# LoRa_ST_v2_0.net
KiCad netlist of a schematic drawn in EAGLE
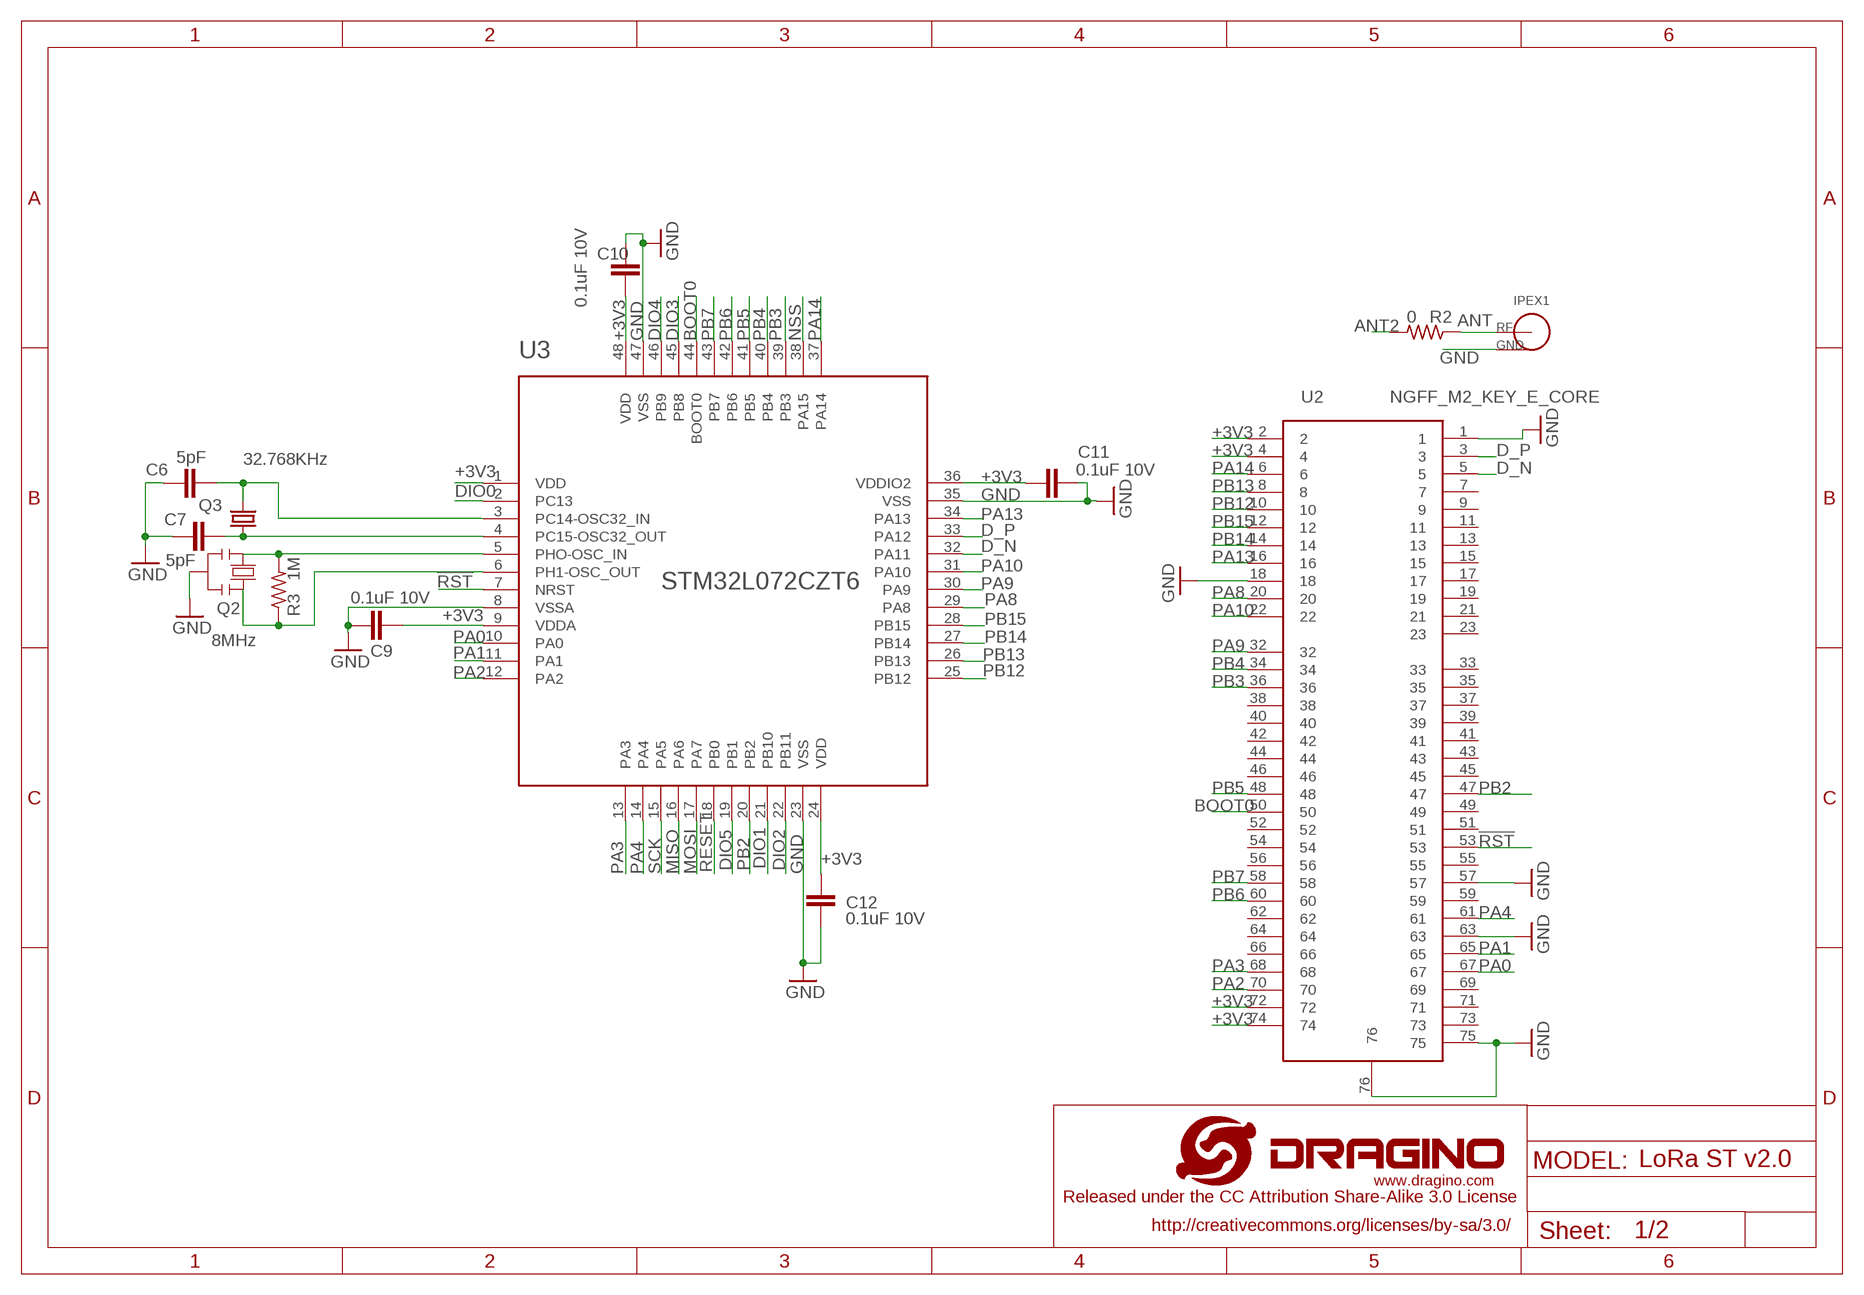
[diagram p0: schematic, sheet 1]
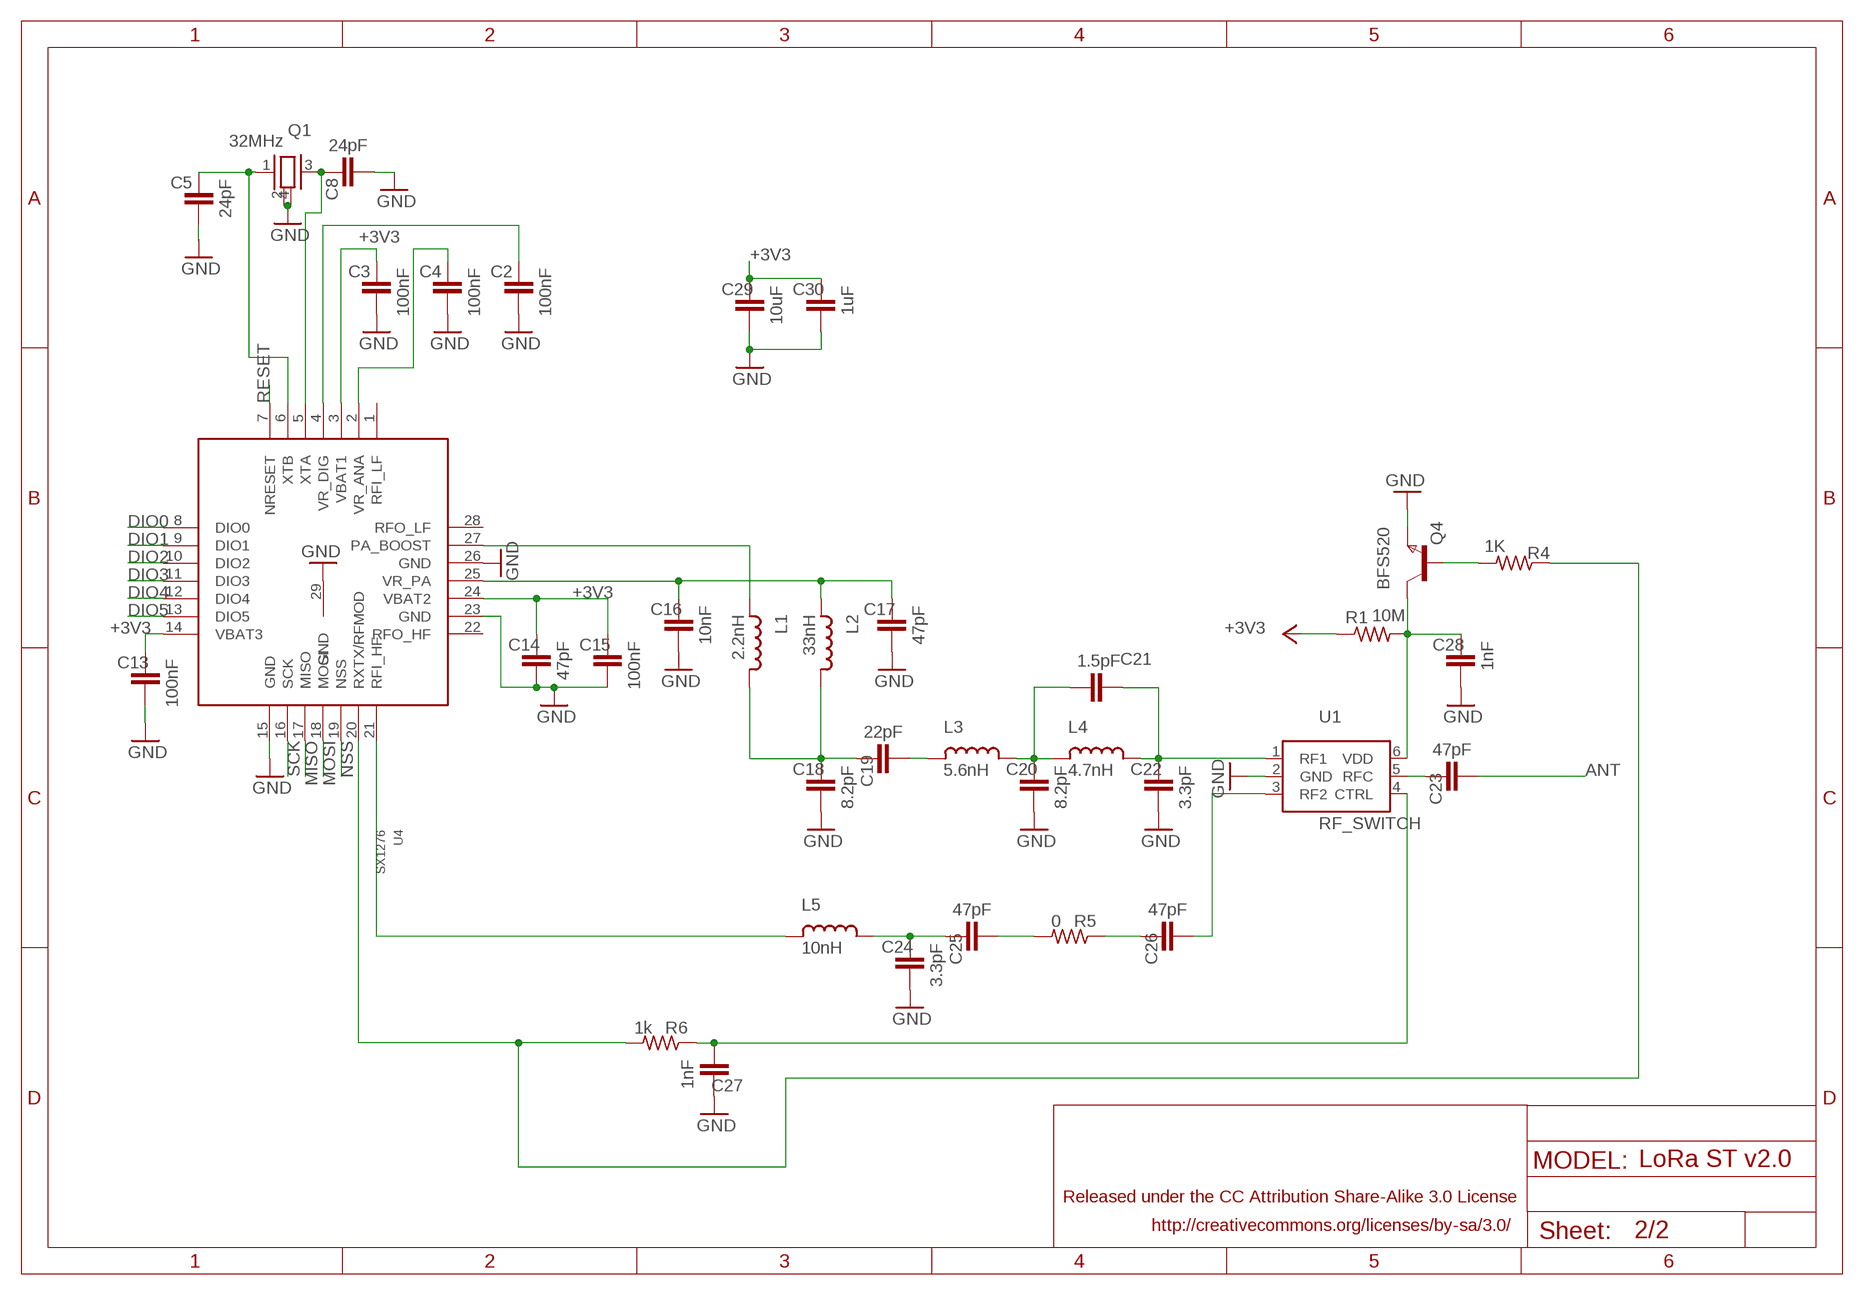
[diagram p1: schematic, sheet 2]

(export (version "E")
  (design (tool "Eeschema 10.0.6"))
  (components
    (comp (ref "C2")
      (value "100nF")
      (footprint "eagle-import:C0402")
      (libsource (lib "eagle-import") (part "C-EUC0402"))
    )
    (comp (ref "C3")
      (value "100nF")
      (footprint "eagle-import:C0402")
      (libsource (lib "eagle-import") (part "C-EUC0402"))
    )
    (comp (ref "C4")
      (value "100nF")
      (footprint "eagle-import:C0402")
      (libsource (lib "eagle-import") (part "C-EUC0402"))
    )
    (comp (ref "C5")
      (value "24pF")
      (footprint "eagle-import:C0402")
      (libsource (lib "eagle-import") (part "C-EUC0402"))
    )
    (comp (ref "C8")
      (value "24pF")
      (footprint "eagle-import:C0402")
      (libsource (lib "eagle-import") (part "C-EUC0402"))
    )
    (comp (ref "C13")
      (value "100nF")
      (footprint "eagle-import:C0402")
      (libsource (lib "eagle-import") (part "C-EUC0402"))
    )
    (comp (ref "C14")
      (value "47pF")
      (footprint "eagle-import:C0402")
      (libsource (lib "eagle-import") (part "C-EUC0402"))
    )
    (comp (ref "C15")
      (value "100nF")
      (footprint "eagle-import:C0402")
      (libsource (lib "eagle-import") (part "C-EUC0402"))
    )
    (comp (ref "C16")
      (value "10nF")
      (footprint "eagle-import:C0402")
      (libsource (lib "eagle-import") (part "C-EUC0402"))
    )
    (comp (ref "C17")
      (value "47pF")
      (footprint "eagle-import:C0402")
      (libsource (lib "eagle-import") (part "C-EUC0402"))
    )
    (comp (ref "C18")
      (value "8.2pF")
      (footprint "eagle-import:C0402")
      (libsource (lib "eagle-import") (part "C-EUC0402"))
    )
    (comp (ref "C19")
      (value "22pF")
      (footprint "eagle-import:C0402")
      (libsource (lib "eagle-import") (part "C-EUC0402"))
    )
    (comp (ref "C20")
      (value "8.2pF")
      (footprint "eagle-import:C0402")
      (libsource (lib "eagle-import") (part "C-EUC0402"))
    )
    (comp (ref "C21")
      (value "1.5pF")
      (footprint "eagle-import:C0402")
      (libsource (lib "eagle-import") (part "C-EUC0402"))
    )
    (comp (ref "C22")
      (value "3.3pF")
      (footprint "eagle-import:C0402")
      (libsource (lib "eagle-import") (part "C-EUC0402"))
    )
    (comp (ref "C23")
      (value "47pF")
      (footprint "eagle-import:C0402")
      (libsource (lib "eagle-import") (part "C-EUC0402"))
    )
    (comp (ref "C24")
      (value "3.3pF")
      (footprint "eagle-import:C0402")
      (libsource (lib "eagle-import") (part "C-EUC0402"))
    )
    (comp (ref "C25")
      (value "47pF")
      (footprint "eagle-import:C0402")
      (libsource (lib "eagle-import") (part "C-EUC0402"))
    )
    (comp (ref "C26")
      (value "47pF")
      (footprint "eagle-import:C0402")
      (libsource (lib "eagle-import") (part "C-EUC0402"))
    )
    (comp (ref "C27")
      (value "1nF")
      (footprint "eagle-import:C0402")
      (libsource (lib "eagle-import") (part "C-EUC0402"))
    )
    (comp (ref "C28")
      (value "1nF")
      (footprint "eagle-import:C0402")
      (libsource (lib "eagle-import") (part "C-EUC0402"))
    )
    (comp (ref "C29")
      (value "10uF")
      (footprint "eagle-import:C0805")
      (libsource (lib "eagle-import") (part "C-EUC0805"))
    )
    (comp (ref "C30")
      (value "1uF")
      (footprint "eagle-import:C0805")
      (libsource (lib "eagle-import") (part "C-EUC0805"))
    )
    (comp (ref "L1")
      (value "2.2nH")
      (footprint "eagle-import:I-0402")
      (libsource (lib "eagle-import") (part "I-EU0402"))
    )
    (comp (ref "L2")
      (value "33nH")
      (footprint "eagle-import:I-0402")
      (libsource (lib "eagle-import") (part "I-EU0402"))
    )
    (comp (ref "L3")
      (value "5.6nH")
      (footprint "eagle-import:I-0402")
      (libsource (lib "eagle-import") (part "I-EU0402"))
    )
    (comp (ref "L4")
      (value "4.7nH")
      (footprint "eagle-import:I-0402")
      (libsource (lib "eagle-import") (part "I-EU0402"))
    )
    (comp (ref "L5")
      (value "10nH")
      (footprint "eagle-import:I-0402")
      (libsource (lib "eagle-import") (part "I-EU0402"))
    )
    (comp (ref "Q1")
      (value "32MHz")
      (footprint "eagle-import:SMD-3225_4P")
      (libsource (lib "eagle-import") (part "Q"))
    )
    (comp (ref "Q4")
      (value "BFS520")
      (footprint "eagle-import:SOT323")
      (fields (field (name "MPN") "DSS4160U-7"))
      (libsource (lib "eagle-import") (part "NPNSOT323"))
    )
    (comp (ref "R1")
      (value "10M")
      (footprint "eagle-import:R0402")
      (libsource (lib "eagle-import") (part "R-US_R0402"))
    )
    (comp (ref "R4")
      (value "1K")
      (footprint "eagle-import:R0402")
      (libsource (lib "eagle-import") (part "R-US_R0402"))
    )
    (comp (ref "R5")
      (value "0")
      (footprint "eagle-import:R0402")
      (libsource (lib "eagle-import") (part "R-US_R0402"))
    )
    (comp (ref "R6")
      (value "1k")
      (footprint "eagle-import:R0402")
      (libsource (lib "eagle-import") (part "R-US_R0402"))
    )
    (comp (ref "U1")
      (value "RF_SWITCH")
      (footprint "eagle-import:SC70-6")
      (libsource (lib "eagle-import") (part "RF_SWITCH"))
    )
    (comp (ref "U4")
      (value "SX1276")
      (footprint "eagle-import:VQFN28_6X6MM")
      (libsource (lib "eagle-import") (part "SX1276"))
    )
    (comp (ref "C6")
      (value "5pF")
      (footprint "eagle-import:C0402")
      (libsource (lib "eagle-import") (part "C-EUC0402"))
    )
    (comp (ref "C7")
      (value "5pF")
      (footprint "eagle-import:C0402")
      (libsource (lib "eagle-import") (part "C-EUC0402"))
    )
    (comp (ref "C9")
      (value "0.1uF 10V")
      (footprint "eagle-import:C0402")
      (libsource (lib "eagle-import") (part "C-EUC0402"))
    )
    (comp (ref "C10")
      (value "0.1uF 10V")
      (footprint "eagle-import:C0402")
      (libsource (lib "eagle-import") (part "C-EUC0402"))
    )
    (comp (ref "C11")
      (value "0.1uF 10V")
      (footprint "eagle-import:C0402")
      (libsource (lib "eagle-import") (part "C-EUC0402"))
    )
    (comp (ref "C12")
      (value "0.1uF 10V")
      (footprint "eagle-import:C0402")
      (libsource (lib "eagle-import") (part "C-EUC0402"))
    )
    (comp (ref "IPEX1")
      (value "I-PEX4")
      (footprint "eagle-import:I-PEX4")
      (libsource (lib "eagle-import") (part "I-PEX4"))
    )
    (comp (ref "Q2")
      (value "8MHz")
      (footprint "eagle-import:RESONATOR")
      (libsource (lib "eagle-import") (part "RESONATORMU"))
    )
    (comp (ref "Q3")
      (value "32.768KHz")
      (footprint "eagle-import:32.768K")
      (libsource (lib "eagle-import") (part "SMD-2012_2P"))
    )
    (comp (ref "R2")
      (value "0")
      (footprint "eagle-import:R0402")
      (libsource (lib "eagle-import") (part "R-US_R0402"))
    )
    (comp (ref "R3")
      (value "1M")
      (footprint "eagle-import:R0402")
      (libsource (lib "eagle-import") (part "R-US_R0402"))
    )
    (comp (ref "U$2")
      (value "LOGO-NEW")
      (footprint "eagle-import:LOGO-SILK-NEW")
      (libsource (lib "eagle-import") (part "LOGO-NEW"))
    )
    (comp (ref "U2")
      (value "NGFF_M2_KEY_E_CORE")
      (footprint "eagle-import:LORA_ST_PCB")
      (libsource (lib "eagle-import") (part "NGFF_M2_KEY_E_CORE"))
    )
    (comp (ref "U3")
      (value "STM32L072CZT6")
      (footprint "eagle-import:LQFP48")
      (libsource (lib "eagle-import") (part "STM32L0XX"))
    )
  )
  (nets
    (net (code "1") (name "+3V3") (class "Default")
      (node (ref "C10") (pin "1") (pinfunction "1_1") (pintype "passive"))
      (node (ref "C11") (pin "2") (pinfunction "2_2") (pintype "passive"))
      (node (ref "C12") (pin "2") (pinfunction "2_2") (pintype "passive"))
      (node (ref "C13") (pin "2") (pinfunction "2_2") (pintype "passive"))
      (node (ref "C14") (pin "2") (pinfunction "2_2") (pintype "passive"))
      (node (ref "C15") (pin "2") (pinfunction "2_2") (pintype "passive"))
      (node (ref "C29") (pin "2") (pinfunction "2_2") (pintype "passive"))
      (node (ref "C3") (pin "2") (pinfunction "2_2") (pintype "passive"))
      (node (ref "C30") (pin "2") (pinfunction "2_2") (pintype "passive"))
      (node (ref "C9") (pin "1") (pinfunction "1_1") (pintype "passive"))
      (node (ref "R1") (pin "1") (pinfunction "1_1") (pintype "passive"))
      (node (ref "U2") (pin "2") (pinfunction "2_2") (pintype "bidirectional"))
      (node (ref "U2") (pin "4") (pinfunction "4_4") (pintype "bidirectional"))
      (node (ref "U2") (pin "72") (pinfunction "72_72") (pintype "bidirectional"))
      (node (ref "U2") (pin "74") (pinfunction "74_74") (pintype "bidirectional"))
      (node (ref "U3") (pin "1") (pinfunction "VDD_1") (pintype "bidirectional"))
      (node (ref "U3") (pin "24") (pinfunction "VDD_24") (pintype "bidirectional"))
      (node (ref "U3") (pin "36") (pinfunction "VDDIO2_36") (pintype "bidirectional"))
      (node (ref "U3") (pin "48") (pinfunction "VDD_48") (pintype "bidirectional"))
      (node (ref "U3") (pin "9") (pinfunction "VDDA_9") (pintype "bidirectional"))
      (node (ref "U4") (pin "14") (pinfunction "VBAT3_14") (pintype "bidirectional"))
      (node (ref "U4") (pin "24") (pinfunction "VBAT2_24") (pintype "bidirectional"))
      (node (ref "U4") (pin "3") (pinfunction "VBAT1_3") (pintype "bidirectional"))
    )
    (net (code "2") (name "ANT") (class "Default")
      (node (ref "C23") (pin "1") (pinfunction "1_1") (pintype "passive"))
      (node (ref "IPEX1") (pin "SIG") (pinfunction "SIG_SIG") (pintype "passive"))
      (node (ref "R2") (pin "1") (pinfunction "1_1") (pintype "passive"))
    )
    (net (code "3") (name "ANT2") (class "Default")
      (node (ref "R2") (pin "2") (pinfunction "2_2") (pintype "passive"))
    )
    (net (code "4") (name "BOOT0") (class "Default")
      (node (ref "U2") (pin "50") (pinfunction "50_50") (pintype "bidirectional"))
      (node (ref "U3") (pin "44") (pinfunction "BOOT0_44") (pintype "bidirectional"))
    )
    (net (code "5") (name "DIO0") (class "Default")
      (node (ref "U3") (pin "2") (pinfunction "PC13_2") (pintype "bidirectional"))
      (node (ref "U4") (pin "8") (pinfunction "DIO0_8") (pintype "bidirectional"))
    )
    (net (code "6") (name "DIO1") (class "Default")
      (node (ref "U3") (pin "21") (pinfunction "PB10_21") (pintype "bidirectional"))
      (node (ref "U4") (pin "9") (pinfunction "DIO1_9") (pintype "bidirectional"))
    )
    (net (code "7") (name "DIO2") (class "Default")
      (node (ref "U3") (pin "22") (pinfunction "PB11_22") (pintype "bidirectional"))
      (node (ref "U4") (pin "10") (pinfunction "DIO2_10") (pintype "bidirectional"))
    )
    (net (code "8") (name "DIO3") (class "Default")
      (node (ref "U3") (pin "45") (pinfunction "PB8_45") (pintype "bidirectional"))
      (node (ref "U4") (pin "11") (pinfunction "DIO3_11") (pintype "bidirectional"))
    )
    (net (code "9") (name "DIO4") (class "Default")
      (node (ref "U3") (pin "46") (pinfunction "PB9_46") (pintype "bidirectional"))
      (node (ref "U4") (pin "12") (pinfunction "DIO4_12") (pintype "bidirectional"))
    )
    (net (code "10") (name "DIO5") (class "Default")
      (node (ref "U3") (pin "19") (pinfunction "PB1_19") (pintype "bidirectional"))
      (node (ref "U4") (pin "13") (pinfunction "DIO5_13") (pintype "bidirectional"))
    )
    (net (code "11") (name "D_N") (class "Default")
      (node (ref "U2") (pin "5") (pinfunction "5_5") (pintype "bidirectional"))
      (node (ref "U3") (pin "32") (pinfunction "PA11_32") (pintype "bidirectional"))
    )
    (net (code "12") (name "D_P") (class "Default")
      (node (ref "U2") (pin "3") (pinfunction "3_3") (pintype "bidirectional"))
      (node (ref "U3") (pin "33") (pinfunction "PA12_33") (pintype "bidirectional"))
    )
    (net (code "13") (name "GND") (class "Default")
      (node (ref "C10") (pin "2") (pinfunction "2_2") (pintype "passive"))
      (node (ref "C11") (pin "1") (pinfunction "1_1") (pintype "passive"))
      (node (ref "C12") (pin "1") (pinfunction "1_1") (pintype "passive"))
      (node (ref "C13") (pin "1") (pinfunction "1_1") (pintype "passive"))
      (node (ref "C14") (pin "1") (pinfunction "1_1") (pintype "passive"))
      (node (ref "C15") (pin "1") (pinfunction "1_1") (pintype "passive"))
      (node (ref "C16") (pin "1") (pinfunction "1_1") (pintype "passive"))
      (node (ref "C17") (pin "1") (pinfunction "1_1") (pintype "passive"))
      (node (ref "C18") (pin "1") (pinfunction "1_1") (pintype "passive"))
      (node (ref "C2") (pin "1") (pinfunction "1_1") (pintype "passive"))
      (node (ref "C20") (pin "1") (pinfunction "1_1") (pintype "passive"))
      (node (ref "C22") (pin "1") (pinfunction "1_1") (pintype "passive"))
      (node (ref "C24") (pin "1") (pinfunction "1_1") (pintype "passive"))
      (node (ref "C27") (pin "2") (pinfunction "2_2") (pintype "passive"))
      (node (ref "C28") (pin "1") (pinfunction "1_1") (pintype "passive"))
      (node (ref "C29") (pin "1") (pinfunction "1_1") (pintype "passive"))
      (node (ref "C3") (pin "1") (pinfunction "1_1") (pintype "passive"))
      (node (ref "C30") (pin "1") (pinfunction "1_1") (pintype "passive"))
      (node (ref "C4") (pin "1") (pinfunction "1_1") (pintype "passive"))
      (node (ref "C5") (pin "1") (pinfunction "1_1") (pintype "passive"))
      (node (ref "C6") (pin "1") (pinfunction "1_1") (pintype "passive"))
      (node (ref "C7") (pin "1") (pinfunction "1_1") (pintype "passive"))
      (node (ref "C8") (pin "1") (pinfunction "1_1") (pintype "passive"))
      (node (ref "C9") (pin "2") (pinfunction "2_2") (pintype "passive"))
      (node (ref "IPEX1") (pin "GND1") (pinfunction "GND_GND1") (pintype "passive"))
      (node (ref "IPEX1") (pin "GND2") (pinfunction "GND_GND2") (pintype "passive"))
      (node (ref "IPEX1") (pin "GND3") (pinfunction "GND_GND3") (pintype "passive"))
      (node (ref "Q1") (pin "2") (pinfunction "P$2_2") (pintype "passive"))
      (node (ref "Q1") (pin "4") (pinfunction "P$4_4") (pintype "passive"))
      (node (ref "Q2") (pin "2") (pinfunction "2_2") (pintype "passive"))
      (node (ref "Q4") (pin "3") (pinfunction "E_3") (pintype "passive"))
      (node (ref "U1") (pin "2") (pinfunction "GND_2") (pintype "bidirectional"))
      (node (ref "U2") (pin "1") (pinfunction "1_1") (pintype "bidirectional"))
      (node (ref "U2") (pin "18") (pinfunction "18_18") (pintype "bidirectional"))
      (node (ref "U2") (pin "57") (pinfunction "57_57") (pintype "bidirectional"))
      (node (ref "U2") (pin "63") (pinfunction "63_63") (pintype "bidirectional"))
      (node (ref "U2") (pin "75") (pinfunction "75_75") (pintype "bidirectional"))
      (node (ref "U2") (pin "76") (pinfunction "76_76") (pintype "bidirectional"))
      (node (ref "U3") (pin "23") (pinfunction "VSS_23") (pintype "bidirectional"))
      (node (ref "U3") (pin "35") (pinfunction "VSS_35") (pintype "bidirectional"))
      (node (ref "U3") (pin "47") (pinfunction "VSS_47") (pintype "bidirectional"))
      (node (ref "U3") (pin "8") (pinfunction "VSSA_8") (pintype "bidirectional"))
      (node (ref "U4") (pin "15") (pinfunction "GND_15") (pintype "bidirectional"))
      (node (ref "U4") (pin "23") (pinfunction "GND_23") (pintype "bidirectional"))
      (node (ref "U4") (pin "26") (pinfunction "GND_26") (pintype "bidirectional"))
      (node (ref "U4") (pin "29") (pinfunction "GND_29") (pintype "bidirectional"))
    )
    (net (code "14") (name "MISO") (class "Default")
      (node (ref "U3") (pin "16") (pinfunction "PA6_16") (pintype "bidirectional"))
      (node (ref "U4") (pin "17") (pinfunction "MISO_17") (pintype "bidirectional"))
    )
    (net (code "15") (name "MOSI") (class "Default")
      (node (ref "U3") (pin "17") (pinfunction "PA7_17") (pintype "bidirectional"))
      (node (ref "U4") (pin "18") (pinfunction "MOSI_18") (pintype "bidirectional"))
    )
    (net (code "16") (name "NSS") (class "Default")
      (node (ref "U3") (pin "38") (pinfunction "PA15_38") (pintype "bidirectional"))
      (node (ref "U4") (pin "19") (pinfunction "NSS_19") (pintype "bidirectional"))
    )
    (net (code "17") (name "Net-(C19-Pad1)") (class "Default")
      (node (ref "C19") (pin "1") (pinfunction "1_1") (pintype "passive"))
      (node (ref "L3") (pin "1") (pinfunction "1_1") (pintype "passive"))
    )
    (net (code "18") (name "Net-(C25-Pad1)") (class "Default")
      (node (ref "C25") (pin "1") (pinfunction "1_1") (pintype "passive"))
      (node (ref "R5") (pin "2") (pinfunction "2_2") (pintype "passive"))
    )
    (net (code "19") (name "Net-(C26-Pad2)") (class "Default")
      (node (ref "C26") (pin "2") (pinfunction "2_2") (pintype "passive"))
      (node (ref "R5") (pin "1") (pinfunction "1_1") (pintype "passive"))
    )
    (net (code "20") (name "Net-(L1-4)") (class "Default")
      (node (ref "C18") (pin "2") (pinfunction "2_2") (pintype "passive"))
      (node (ref "C19") (pin "2") (pinfunction "2_2") (pintype "passive"))
      (node (ref "L1") (pin "2") (pinfunction "4_2") (pintype "passive"))
      (node (ref "L2") (pin "2") (pinfunction "4_2") (pintype "passive"))
    )
    (net (code "21") (name "Net-(L3-4)") (class "Default")
      (node (ref "C20") (pin "2") (pinfunction "2_2") (pintype "passive"))
      (node (ref "C21") (pin "2") (pinfunction "2_2") (pintype "passive"))
      (node (ref "L3") (pin "2") (pinfunction "4_2") (pintype "passive"))
      (node (ref "L4") (pin "1") (pinfunction "1_1") (pintype "passive"))
    )
    (net (code "22") (name "Net-(L4-4)") (class "Default")
      (node (ref "C21") (pin "1") (pinfunction "1_1") (pintype "passive"))
      (node (ref "C22") (pin "2") (pinfunction "2_2") (pintype "passive"))
      (node (ref "L4") (pin "2") (pinfunction "4_2") (pintype "passive"))
      (node (ref "U1") (pin "1") (pinfunction "RF1_1") (pintype "bidirectional"))
    )
    (net (code "23") (name "Net-(L5-4)") (class "Default")
      (node (ref "C24") (pin "2") (pinfunction "2_2") (pintype "passive"))
      (node (ref "C25") (pin "2") (pinfunction "2_2") (pintype "passive"))
      (node (ref "L5") (pin "2") (pinfunction "4_2") (pintype "passive"))
    )
    (net (code "24") (name "Net-(Q1-P$1)") (class "Default")
      (node (ref "C5") (pin "2") (pinfunction "2_2") (pintype "passive"))
      (node (ref "Q1") (pin "1") (pinfunction "P$1_1") (pintype "passive"))
      (node (ref "U4") (pin "6") (pinfunction "XTB_6") (pintype "bidirectional"))
    )
    (net (code "25") (name "Net-(Q1-P$3)") (class "Default")
      (node (ref "C8") (pin "2") (pinfunction "2_2") (pintype "passive"))
      (node (ref "Q1") (pin "3") (pinfunction "P$3_3") (pintype "passive"))
      (node (ref "U4") (pin "5") (pinfunction "XTA_5") (pintype "bidirectional"))
    )
    (net (code "26") (name "Net-(Q3-1)") (class "Default")
      (node (ref "C7") (pin "2") (pinfunction "2_2") (pintype "passive"))
      (node (ref "Q3") (pin "3") (pinfunction "1_3") (pintype "passive"))
      (node (ref "U3") (pin "4") (pinfunction "PC15-OSC32_OUT_4") (pintype "bidirectional"))
    )
    (net (code "27") (name "Net-(Q3-2)") (class "Default")
      (node (ref "C6") (pin "2") (pinfunction "2_2") (pintype "passive"))
      (node (ref "Q3") (pin "4") (pinfunction "2_4") (pintype "passive"))
      (node (ref "U3") (pin "3") (pinfunction "PC14-OSC32_IN_3") (pintype "bidirectional"))
    )
    (net (code "28") (name "Net-(Q4-B)") (class "Default")
      (node (ref "Q4") (pin "2") (pinfunction "B_2") (pintype "passive"))
      (node (ref "R4") (pin "2") (pinfunction "2_2") (pintype "passive"))
    )
    (net (code "29") (name "Net-(Q4-C)") (class "Default")
      (node (ref "C28") (pin "2") (pinfunction "2_2") (pintype "passive"))
      (node (ref "Q4") (pin "1") (pinfunction "C_1") (pintype "passive"))
      (node (ref "R1") (pin "2") (pinfunction "2_2") (pintype "passive"))
      (node (ref "U1") (pin "6") (pinfunction "VDD_6") (pintype "bidirectional"))
    )
    (net (code "30") (name "Net-(U1-CTRL)") (class "Default")
      (node (ref "C27") (pin "1") (pinfunction "1_1") (pintype "passive"))
      (node (ref "R6") (pin "1") (pinfunction "1_1") (pintype "passive"))
      (node (ref "U1") (pin "4") (pinfunction "CTRL_4") (pintype "bidirectional"))
    )
    (net (code "31") (name "Net-(U1-RF2)") (class "Default")
      (node (ref "C26") (pin "1") (pinfunction "1_1") (pintype "passive"))
      (node (ref "U1") (pin "3") (pinfunction "RF2_3") (pintype "bidirectional"))
    )
    (net (code "32") (name "Net-(U1-RFC)") (class "Default")
      (node (ref "C23") (pin "2") (pinfunction "2_2") (pintype "passive"))
      (node (ref "U1") (pin "5") (pinfunction "RFC_5") (pintype "bidirectional"))
    )
    (net (code "33") (name "Net-(U3-PH1-OSC_OUT)") (class "Default")
      (node (ref "Q2") (pin "3") (pinfunction "3_3") (pintype "passive"))
      (node (ref "R3") (pin "1") (pinfunction "1_1") (pintype "passive"))
      (node (ref "U3") (pin "6") (pinfunction "PH1-OSC_OUT_6") (pintype "bidirectional"))
    )
    (net (code "34") (name "Net-(U3-PHO-OSC_IN)") (class "Default")
      (node (ref "Q2") (pin "1") (pinfunction "1_1") (pintype "passive"))
      (node (ref "R3") (pin "2") (pinfunction "2_2") (pintype "passive"))
      (node (ref "U3") (pin "5") (pinfunction "PHO-OSC_IN_5") (pintype "bidirectional"))
    )
    (net (code "35") (name "Net-(U4-PA_BOOST)") (class "Default")
      (node (ref "L1") (pin "1") (pinfunction "1_1") (pintype "passive"))
      (node (ref "U4") (pin "27") (pinfunction "PA_BOOST_27") (pintype "bidirectional"))
    )
    (net (code "36") (name "Net-(U4-RFI_HF)") (class "Default")
      (node (ref "L5") (pin "1") (pinfunction "1_1") (pintype "passive"))
      (node (ref "U4") (pin "21") (pinfunction "RFI_HF_21") (pintype "bidirectional"))
    )
    (net (code "37") (name "Net-(U4-RXTX{slash}RFMOD)") (class "Default")
      (node (ref "R4") (pin "1") (pinfunction "1_1") (pintype "passive"))
      (node (ref "R6") (pin "2") (pinfunction "2_2") (pintype "passive"))
      (node (ref "U4") (pin "20") (pinfunction "RXTX/RFMOD_20") (pintype "bidirectional"))
    )
    (net (code "38") (name "Net-(U4-VR_ANA)") (class "Default")
      (node (ref "C4") (pin "2") (pinfunction "2_2") (pintype "passive"))
      (node (ref "U4") (pin "2") (pinfunction "VR_ANA_2") (pintype "bidirectional"))
    )
    (net (code "39") (name "Net-(U4-VR_DIG)") (class "Default")
      (node (ref "C2") (pin "2") (pinfunction "2_2") (pintype "passive"))
      (node (ref "U4") (pin "4") (pinfunction "VR_DIG_4") (pintype "bidirectional"))
    )
    (net (code "40") (name "Net-(U4-VR_PA)") (class "Default")
      (node (ref "C16") (pin "2") (pinfunction "2_2") (pintype "passive"))
      (node (ref "C17") (pin "2") (pinfunction "2_2") (pintype "passive"))
      (node (ref "L2") (pin "1") (pinfunction "1_1") (pintype "passive"))
      (node (ref "U4") (pin "25") (pinfunction "VR_PA_25") (pintype "bidirectional"))
    )
    (net (code "41") (name "PA0") (class "Default")
      (node (ref "U2") (pin "67") (pinfunction "67_67") (pintype "bidirectional"))
      (node (ref "U3") (pin "10") (pinfunction "PA0_10") (pintype "bidirectional"))
    )
    (net (code "42") (name "PA1") (class "Default")
      (node (ref "U2") (pin "65") (pinfunction "65_65") (pintype "bidirectional"))
      (node (ref "U3") (pin "11") (pinfunction "PA1_11") (pintype "bidirectional"))
    )
    (net (code "43") (name "PA2") (class "Default")
      (node (ref "U2") (pin "70") (pinfunction "70_70") (pintype "bidirectional"))
      (node (ref "U3") (pin "12") (pinfunction "PA2_12") (pintype "bidirectional"))
    )
    (net (code "44") (name "PA3") (class "Default")
      (node (ref "U2") (pin "68") (pinfunction "68_68") (pintype "bidirectional"))
      (node (ref "U3") (pin "13") (pinfunction "PA3_13") (pintype "bidirectional"))
    )
    (net (code "45") (name "PA4") (class "Default")
      (node (ref "U2") (pin "61") (pinfunction "61_61") (pintype "bidirectional"))
      (node (ref "U3") (pin "14") (pinfunction "PA4_14") (pintype "bidirectional"))
    )
    (net (code "46") (name "PA8") (class "Default")
      (node (ref "U2") (pin "20") (pinfunction "20_20") (pintype "bidirectional"))
      (node (ref "U3") (pin "29") (pinfunction "PA8_29") (pintype "bidirectional"))
    )
    (net (code "47") (name "PA9") (class "Default")
      (node (ref "U2") (pin "32") (pinfunction "32_32") (pintype "bidirectional"))
      (node (ref "U3") (pin "30") (pinfunction "PA9_30") (pintype "bidirectional"))
    )
    (net (code "48") (name "PA10") (class "Default")
      (node (ref "U2") (pin "22") (pinfunction "22_22") (pintype "bidirectional"))
      (node (ref "U3") (pin "31") (pinfunction "PA10_31") (pintype "bidirectional"))
    )
    (net (code "49") (name "PA13") (class "Default")
      (node (ref "U2") (pin "16") (pinfunction "16_16") (pintype "bidirectional"))
      (node (ref "U3") (pin "34") (pinfunction "PA13_34") (pintype "bidirectional"))
    )
    (net (code "50") (name "PA14") (class "Default")
      (node (ref "U2") (pin "6") (pinfunction "6_6") (pintype "bidirectional"))
      (node (ref "U3") (pin "37") (pinfunction "PA14_37") (pintype "bidirectional"))
    )
    (net (code "51") (name "PB2") (class "Default")
      (node (ref "U2") (pin "47") (pinfunction "47_47") (pintype "bidirectional"))
      (node (ref "U3") (pin "20") (pinfunction "PB2_20") (pintype "bidirectional"))
    )
    (net (code "52") (name "PB3") (class "Default")
      (node (ref "U2") (pin "36") (pinfunction "36_36") (pintype "bidirectional"))
      (node (ref "U3") (pin "39") (pinfunction "PB3_39") (pintype "bidirectional"))
    )
    (net (code "53") (name "PB4") (class "Default")
      (node (ref "U2") (pin "34") (pinfunction "34_34") (pintype "bidirectional"))
      (node (ref "U3") (pin "40") (pinfunction "PB4_40") (pintype "bidirectional"))
    )
    (net (code "54") (name "PB5") (class "Default")
      (node (ref "U2") (pin "48") (pinfunction "48_48") (pintype "bidirectional"))
      (node (ref "U3") (pin "41") (pinfunction "PB5_41") (pintype "bidirectional"))
    )
    (net (code "55") (name "PB6") (class "Default")
      (node (ref "U2") (pin "60") (pinfunction "60_60") (pintype "bidirectional"))
      (node (ref "U3") (pin "42") (pinfunction "PB6_42") (pintype "bidirectional"))
    )
    (net (code "56") (name "PB7") (class "Default")
      (node (ref "U2") (pin "58") (pinfunction "58_58") (pintype "bidirectional"))
      (node (ref "U3") (pin "43") (pinfunction "PB7_43") (pintype "bidirectional"))
    )
    (net (code "57") (name "PB12") (class "Default")
      (node (ref "U2") (pin "10") (pinfunction "10_10") (pintype "bidirectional"))
      (node (ref "U3") (pin "25") (pinfunction "PB12_25") (pintype "bidirectional"))
    )
    (net (code "58") (name "PB13") (class "Default")
      (node (ref "U2") (pin "8") (pinfunction "8_8") (pintype "bidirectional"))
      (node (ref "U3") (pin "26") (pinfunction "PB13_26") (pintype "bidirectional"))
    )
    (net (code "59") (name "PB14") (class "Default")
      (node (ref "U2") (pin "14") (pinfunction "14_14") (pintype "bidirectional"))
      (node (ref "U3") (pin "27") (pinfunction "PB14_27") (pintype "bidirectional"))
    )
    (net (code "60") (name "PB15") (class "Default")
      (node (ref "U2") (pin "12") (pinfunction "12_12") (pintype "bidirectional"))
      (node (ref "U3") (pin "28") (pinfunction "PB15_28") (pintype "bidirectional"))
    )
    (net (code "61") (name "RESET") (class "Default")
      (node (ref "U3") (pin "18") (pinfunction "PB0_18") (pintype "bidirectional"))
      (node (ref "U4") (pin "7") (pinfunction "NRESET_7") (pintype "bidirectional"))
    )
    (net (code "62") (name "SCK") (class "Default")
      (node (ref "U3") (pin "15") (pinfunction "PA5_15") (pintype "bidirectional"))
      (node (ref "U4") (pin "16") (pinfunction "SCK_16") (pintype "bidirectional"))
    )
    (net (code "63") (name "unconnected-(U2-Pad7)") (class "Default")
      (node (ref "U2") (pin "7") (pinfunction "7_7") (pintype "bidirectional"))
    )
    (net (code "64") (name "unconnected-(U2-Pad9)") (class "Default")
      (node (ref "U2") (pin "9") (pinfunction "9_9") (pintype "bidirectional"))
    )
    (net (code "65") (name "unconnected-(U2-Pad11)") (class "Default")
      (node (ref "U2") (pin "11") (pinfunction "11_11") (pintype "bidirectional"))
    )
    (net (code "66") (name "unconnected-(U2-Pad13)") (class "Default")
      (node (ref "U2") (pin "13") (pinfunction "13_13") (pintype "bidirectional"))
    )
    (net (code "67") (name "unconnected-(U2-Pad15)") (class "Default")
      (node (ref "U2") (pin "15") (pinfunction "15_15") (pintype "bidirectional"))
    )
    (net (code "68") (name "unconnected-(U2-Pad17)") (class "Default")
      (node (ref "U2") (pin "17") (pinfunction "17_17") (pintype "bidirectional"))
    )
    (net (code "69") (name "unconnected-(U2-Pad19)") (class "Default")
      (node (ref "U2") (pin "19") (pinfunction "19_19") (pintype "bidirectional"))
    )
    (net (code "70") (name "unconnected-(U2-Pad21)") (class "Default")
      (node (ref "U2") (pin "21") (pinfunction "21_21") (pintype "bidirectional"))
    )
    (net (code "71") (name "unconnected-(U2-Pad23)") (class "Default")
      (node (ref "U2") (pin "23") (pinfunction "23_23") (pintype "bidirectional"))
    )
    (net (code "72") (name "unconnected-(U2-Pad33)") (class "Default")
      (node (ref "U2") (pin "33") (pinfunction "33_33") (pintype "bidirectional"))
    )
    (net (code "73") (name "unconnected-(U2-Pad35)") (class "Default")
      (node (ref "U2") (pin "35") (pinfunction "35_35") (pintype "bidirectional"))
    )
    (net (code "74") (name "unconnected-(U2-Pad37)") (class "Default")
      (node (ref "U2") (pin "37") (pinfunction "37_37") (pintype "bidirectional"))
    )
    (net (code "75") (name "unconnected-(U2-Pad38)") (class "Default")
      (node (ref "U2") (pin "38") (pinfunction "38_38") (pintype "bidirectional"))
    )
    (net (code "76") (name "unconnected-(U2-Pad39)") (class "Default")
      (node (ref "U2") (pin "39") (pinfunction "39_39") (pintype "bidirectional"))
    )
    (net (code "77") (name "unconnected-(U2-Pad40)") (class "Default")
      (node (ref "U2") (pin "40") (pinfunction "40_40") (pintype "bidirectional"))
    )
    (net (code "78") (name "unconnected-(U2-Pad41)") (class "Default")
      (node (ref "U2") (pin "41") (pinfunction "41_41") (pintype "bidirectional"))
    )
    (net (code "79") (name "unconnected-(U2-Pad42)") (class "Default")
      (node (ref "U2") (pin "42") (pinfunction "42_42") (pintype "bidirectional"))
    )
    (net (code "80") (name "unconnected-(U2-Pad43)") (class "Default")
      (node (ref "U2") (pin "43") (pinfunction "43_43") (pintype "bidirectional"))
    )
    (net (code "81") (name "unconnected-(U2-Pad44)") (class "Default")
      (node (ref "U2") (pin "44") (pinfunction "44_44") (pintype "bidirectional"))
    )
    (net (code "82") (name "unconnected-(U2-Pad45)") (class "Default")
      (node (ref "U2") (pin "45") (pinfunction "45_45") (pintype "bidirectional"))
    )
    (net (code "83") (name "unconnected-(U2-Pad46)") (class "Default")
      (node (ref "U2") (pin "46") (pinfunction "46_46") (pintype "bidirectional"))
    )
    (net (code "84") (name "unconnected-(U2-Pad49)") (class "Default")
      (node (ref "U2") (pin "49") (pinfunction "49_49") (pintype "bidirectional"))
    )
    (net (code "85") (name "unconnected-(U2-Pad51)") (class "Default")
      (node (ref "U2") (pin "51") (pinfunction "51_51") (pintype "bidirectional"))
    )
    (net (code "86") (name "unconnected-(U2-Pad52)") (class "Default")
      (node (ref "U2") (pin "52") (pinfunction "52_52") (pintype "bidirectional"))
    )
    (net (code "87") (name "unconnected-(U2-Pad54)") (class "Default")
      (node (ref "U2") (pin "54") (pinfunction "54_54") (pintype "bidirectional"))
    )
    (net (code "88") (name "unconnected-(U2-Pad55)") (class "Default")
      (node (ref "U2") (pin "55") (pinfunction "55_55") (pintype "bidirectional"))
    )
    (net (code "89") (name "unconnected-(U2-Pad56)") (class "Default")
      (node (ref "U2") (pin "56") (pinfunction "56_56") (pintype "bidirectional"))
    )
    (net (code "90") (name "unconnected-(U2-Pad59)") (class "Default")
      (node (ref "U2") (pin "59") (pinfunction "59_59") (pintype "bidirectional"))
    )
    (net (code "91") (name "unconnected-(U2-Pad62)") (class "Default")
      (node (ref "U2") (pin "62") (pinfunction "62_62") (pintype "bidirectional"))
    )
    (net (code "92") (name "unconnected-(U2-Pad64)") (class "Default")
      (node (ref "U2") (pin "64") (pinfunction "64_64") (pintype "bidirectional"))
    )
    (net (code "93") (name "unconnected-(U2-Pad66)") (class "Default")
      (node (ref "U2") (pin "66") (pinfunction "66_66") (pintype "bidirectional"))
    )
    (net (code "94") (name "unconnected-(U2-Pad69)") (class "Default")
      (node (ref "U2") (pin "69") (pinfunction "69_69") (pintype "bidirectional"))
    )
    (net (code "95") (name "unconnected-(U2-Pad71)") (class "Default")
      (node (ref "U2") (pin "71") (pinfunction "71_71") (pintype "bidirectional"))
    )
    (net (code "96") (name "unconnected-(U2-Pad73)") (class "Default")
      (node (ref "U2") (pin "73") (pinfunction "73_73") (pintype "bidirectional"))
    )
    (net (code "97") (name "unconnected-(U4-RFI_LF-Pad1)") (class "Default")
      (node (ref "U4") (pin "1") (pinfunction "RFI_LF_1") (pintype "bidirectional"))
    )
    (net (code "98") (name "unconnected-(U4-RFO_HF-Pad22)") (class "Default")
      (node (ref "U4") (pin "22") (pinfunction "RFO_HF_22") (pintype "bidirectional"))
    )
    (net (code "99") (name "unconnected-(U4-RFO_LF-Pad28)") (class "Default")
      (node (ref "U4") (pin "28") (pinfunction "RFO_LF_28") (pintype "bidirectional"))
    )
    (net (code "100") (name "~{RST}") (class "Default")
      (node (ref "U2") (pin "53") (pinfunction "53_53") (pintype "bidirectional"))
      (node (ref "U3") (pin "7") (pinfunction "NRST_7") (pintype "bidirectional"))
    )
  )
)
